# MC33797.net
KiCad netlist of a schematic drawn in Altium Designer
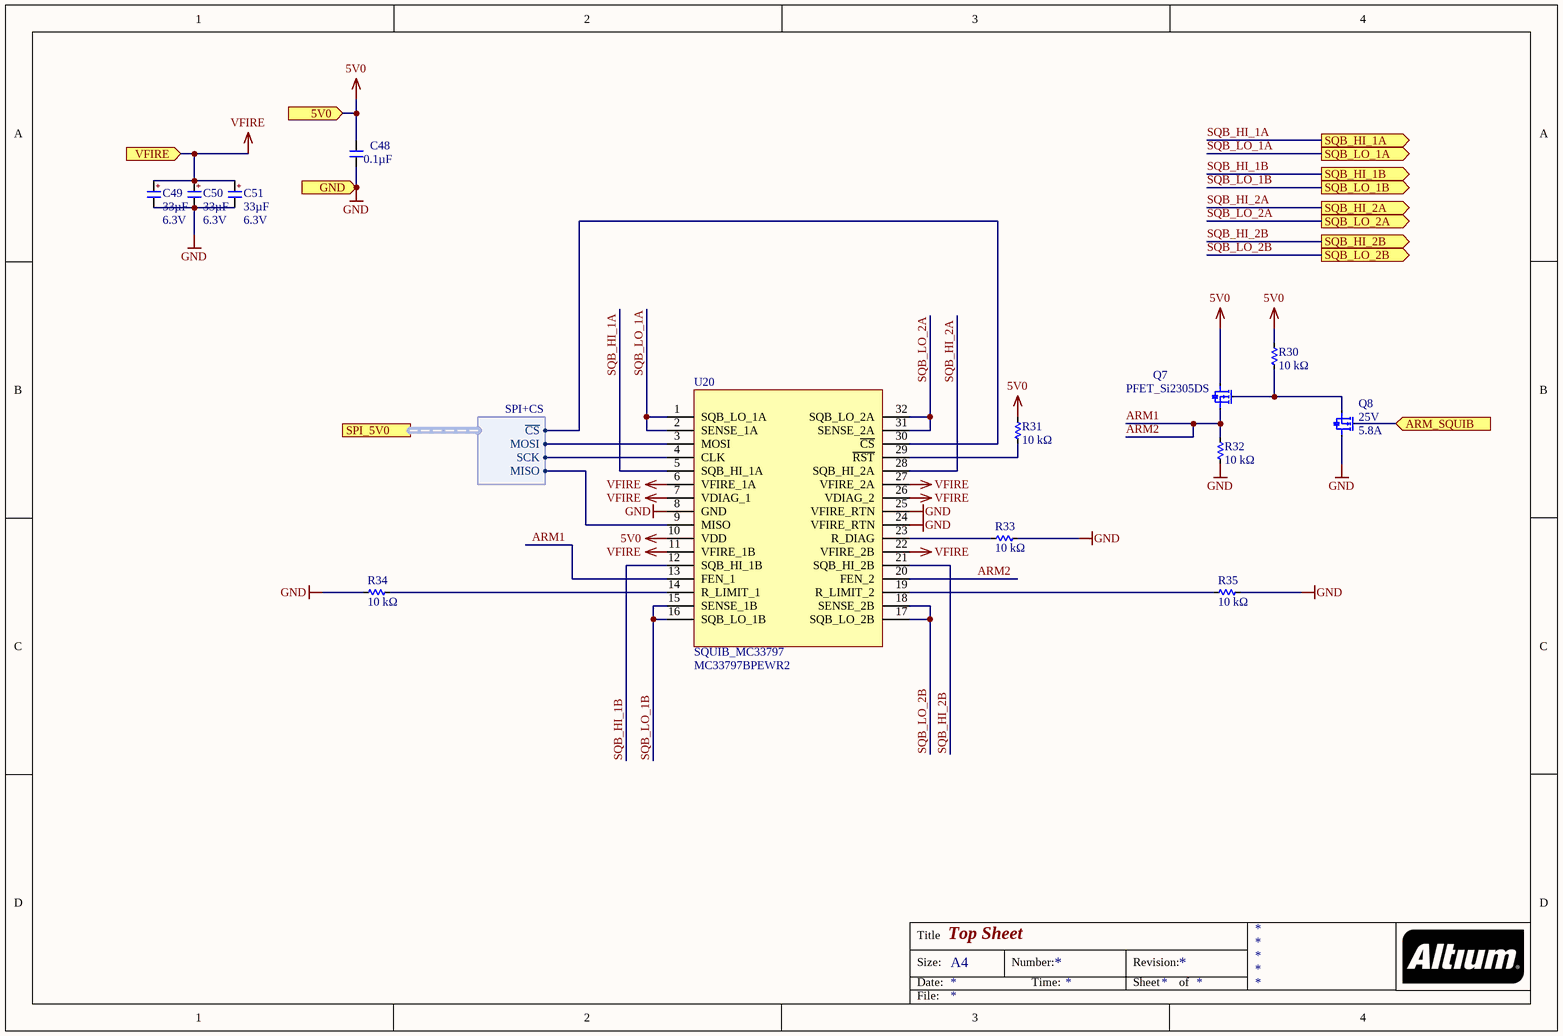
[diagram p0: MC33797.SchDoc]

(export (version "E")
  (design (tool "Eeschema 10.0.6"))
  (components
    (comp (ref "C48")
      (value "CAP_CER_100NF_100V")
      (footprint "C0603")
      (description "CAP CER 0.1UF 100V X7S 0603")
      (fields
        (field (name "MANUFACTURER") "TDK Corporation")
        (field (name "TOLERANCE") "±10%")
        (field (name "CAPACITANCE") "0.1µF")
      )
      (libsource (lib "") (part "Symbol_1"))
    )
    (comp (ref "C49")
      (value "CAP_TANT_33UF")
      (footprint "C1206P")
      (fields
        (field (name "MANUFACTURER") "AVX Corporation")
        (field (name "MANUFACTURER PART NUMBER") "TPSA336K006R0600")
        (field (name "TOLERANCE") "±10%")
        (field (name "CAPACITANCE") "33µF")
        (field (name "VOLTAGE - RATED") "6.3V")
      )
      (libsource (lib "Stanford Student Space Initiative") (part "CAP_TANT_33UF"))
    )
    (comp (ref "C50")
      (value "CAP_TANT_33UF")
      (footprint "C1206P")
      (fields
        (field (name "MANUFACTURER") "AVX Corporation")
        (field (name "MANUFACTURER PART NUMBER") "TPSA336K006R0600")
        (field (name "TOLERANCE") "±10%")
        (field (name "CAPACITANCE") "33µF")
        (field (name "VOLTAGE - RATED") "6.3V")
      )
      (libsource (lib "Stanford Student Space Initiative") (part "CAP_TANT_33UF"))
    )
    (comp (ref "C51")
      (value "CAP_TANT_33UF")
      (footprint "C1206P")
      (fields
        (field (name "MANUFACTURER") "AVX Corporation")
        (field (name "MANUFACTURER PART NUMBER") "TPSA336K006R0600")
        (field (name "TOLERANCE") "±10%")
        (field (name "CAPACITANCE") "33µF")
        (field (name "VOLTAGE - RATED") "6.3V")
      )
      (libsource (lib "Stanford Student Space Initiative") (part "CAP_TANT_33UF"))
    )
    (comp (ref "Q7")
      (value "PFET_Si2305DS")
      (footprint "3SOT23")
      (description "MOSFET P-CH")
      (libsource (lib "Stanford Student Space Initiative") (part "PFET_Si2305DS"))
    )
    (comp (ref "Q8")
      (value "NFET_IRFML8244TRPBF")
      (footprint "3SOT23")
      (description "MOSFET N-CH 25V 5.8A SOT23")
      (fields
        (field (name "MANUFACTURER") "International Rectifier")
        (field (name "MANUFACTURER PART NUMBER") "IRFML8244TRPBF")
        (field (name "DRAIN TO SOURCE VOLTAGE (VDSS)") "25V")
        (field (name "CURRENT - CONTINUOUS DRAIN (ID) @ 25° C") "5.8A")
      )
      (libsource (lib "Stanford Student Space Initiative") (part "Symbol"))
    )
    (comp (ref "R30")
      (value "311-10.0KHRCT-ND")
      (footprint "R0603")
      (description "RES SMD 10K OHM 1% 1/10W 0603")
      (fields
        (field (name "RESISTANCE") "10 kΩ")
        (field (name "MANUFACTURER PART NUMBER") "RC0603FR-0710KL")
        (field (name "MANUFACTURER") "Yageo")
      )
      (libsource (lib "Stanford Student Space Initiative") (part "__template_resistor"))
    )
    (comp (ref "R31")
      (value "311-10.0KHRCT-ND")
      (footprint "R0603")
      (description "RES SMD 10K OHM 1% 1/10W 0603")
      (fields
        (field (name "RESISTANCE") "10 kΩ")
        (field (name "MANUFACTURER PART NUMBER") "RC0603FR-0710KL")
        (field (name "MANUFACTURER") "Yageo")
      )
      (libsource (lib "Stanford Student Space Initiative") (part "__template_resistor"))
    )
    (comp (ref "R32")
      (value "311-10.0KHRCT-ND")
      (footprint "R0603")
      (description "RES SMD 10K OHM 1% 1/10W 0603")
      (fields
        (field (name "RESISTANCE") "10 kΩ")
        (field (name "MANUFACTURER PART NUMBER") "RC0603FR-0710KL")
        (field (name "MANUFACTURER") "Yageo")
      )
      (libsource (lib "Stanford Student Space Initiative") (part "__template_resistor"))
    )
    (comp (ref "R33")
      (value "311-10.0KHRCT-ND")
      (footprint "R0603")
      (description "RES SMD 10K OHM 1% 1/10W 0603")
      (fields
        (field (name "RESISTANCE") "10 kΩ")
        (field (name "MANUFACTURER PART NUMBER") "RC0603FR-0710KL")
        (field (name "MANUFACTURER") "Yageo")
      )
      (libsource (lib "Stanford Student Space Initiative") (part "__template_resistor"))
    )
    (comp (ref "R34")
      (value "311-10.0KHRCT-ND")
      (footprint "R0603")
      (description "RES SMD 10K OHM 1% 1/10W 0603")
      (fields
        (field (name "RESISTANCE") "10 kΩ")
        (field (name "MANUFACTURER PART NUMBER") "RC0603FR-0710KL")
        (field (name "MANUFACTURER") "Yageo")
      )
      (libsource (lib "Stanford Student Space Initiative") (part "__template_resistor"))
    )
    (comp (ref "R35")
      (value "311-10.0KHRCT-ND")
      (footprint "R0603")
      (description "RES SMD 10K OHM 1% 1/10W 0603")
      (fields
        (field (name "RESISTANCE") "10 kΩ")
        (field (name "MANUFACTURER PART NUMBER") "RC0603FR-0710KL")
        (field (name "MANUFACTURER") "Yageo")
      )
      (libsource (lib "Stanford Student Space Initiative") (part "__template_resistor"))
    )
    (comp (ref "U20")
      (value "SQUIB_MC33797")
      (footprint "SOT1762-1")
      (fields
        (field (name "MANUFACTURER") "NXP USA Inc.")
        (field (name "MANUFACTURER PART NUMBER") "MC33797BPEWR2")
      )
      (libsource (lib "Stanford Student Space Initiative") (part "SQUIB_MC33797"))
    )
  )
  (nets
    (net (code "2") (name "/ARM1") (class "Default")
      (node (ref "Q7") (pin "2") (pintype "passive"))
      (node (ref "R32") (pin "2") (pinfunction "2_2") (pintype "passive"))
      (node (ref "U20") (pin "13") (pinfunction "FEN_1_13") (pintype "passive"))
      (node (ref "U20") (pin "20") (pinfunction "FEN_2_20") (pintype "passive"))
    )
    (net (code "3") (name "/ARM_SQUIB") (class "Default") (node (ref "Q8") (pin "1") (pintype "passive")))
    (net (code "4") (name "/MISO") (class "Default")
      (node (ref "U20") (pin "9") (pinfunction "MISO_9") (pintype "passive"))
    )
    (net (code "5") (name "/MOSI") (class "Default")
      (node (ref "U20") (pin "3") (pinfunction "MOSI_3") (pintype "passive"))
    )
    (net (code "6") (name "/SCK") (class "Default")
      (node (ref "U20") (pin "4") (pinfunction "CLK_4") (pintype "passive"))
    )
    (net (code "7") (name "/SQB_HI_1A") (class "Default")
      (node (ref "U20") (pin "5") (pinfunction "SQB_HI_1A_5") (pintype "passive"))
    )
    (net (code "8") (name "/SQB_HI_1B") (class "Default")
      (node (ref "U20") (pin "12") (pinfunction "SQB_HI_1B_12") (pintype "passive"))
    )
    (net (code "9") (name "/SQB_HI_2A") (class "Default")
      (node (ref "U20") (pin "28") (pinfunction "SQB_HI_2A_28") (pintype "passive"))
    )
    (net (code "10") (name "/SQB_HI_2B") (class "Default")
      (node (ref "U20") (pin "21") (pinfunction "SQB_HI_2B_21") (pintype "passive"))
    )
    (net (code "11") (name "/SQB_LO_1A") (class "Default")
      (node (ref "U20") (pin "1") (pinfunction "SQB_LO_1A_1") (pintype "passive"))
      (node (ref "U20") (pin "2") (pinfunction "SENSE_1A_2") (pintype "passive"))
    )
    (net (code "12") (name "/SQB_LO_1B") (class "Default")
      (node (ref "U20") (pin "15") (pinfunction "SENSE_1B_15") (pintype "passive"))
      (node (ref "U20") (pin "16") (pinfunction "SQB_LO_1B_16") (pintype "passive"))
    )
    (net (code "13") (name "/SQB_LO_2A") (class "Default")
      (node (ref "U20") (pin "31") (pinfunction "SENSE_2A_31") (pintype "passive"))
      (node (ref "U20") (pin "32") (pinfunction "SQB_LO_2A_32") (pintype "passive"))
    )
    (net (code "14") (name "/SQB_LO_2B") (class "Default")
      (node (ref "U20") (pin "17") (pinfunction "SQB_LO_2B_17") (pintype "passive"))
      (node (ref "U20") (pin "18") (pinfunction "SENSE_2B_18") (pintype "passive"))
    )
    (net (code "16") (name "/~{CS}") (class "Default")
      (node (ref "U20") (pin "30") (pinfunction "~{CS}_30") (pintype "passive"))
    )
    (net (code "17") (name "5V0") (class "Default")
      (node (ref "C48") (pin "1") (pintype "passive"))
      (node (ref "Q7") (pin "3") (pintype "passive"))
      (node (ref "R30") (pin "2") (pinfunction "2_2") (pintype "passive"))
      (node (ref "R31") (pin "2") (pinfunction "2_2") (pintype "passive"))
      (node (ref "U20") (pin "10") (pinfunction "VDD_10") (pintype "passive"))
    )
    (net (code "18") (name "GND") (class "Default")
      (node (ref "C48") (pin "2") (pintype "passive"))
      (node (ref "C49") (pin "2") (pintype "passive"))
      (node (ref "C50") (pin "2") (pintype "passive"))
      (node (ref "C51") (pin "2") (pintype "passive"))
      (node (ref "Q8") (pin "3") (pintype "passive"))
      (node (ref "R32") (pin "1") (pinfunction "1_1") (pintype "passive"))
      (node (ref "R33") (pin "2") (pinfunction "2_2") (pintype "passive"))
      (node (ref "R34") (pin "1") (pinfunction "1_1") (pintype "passive"))
      (node (ref "R35") (pin "2") (pinfunction "2_2") (pintype "passive"))
      (node (ref "U20") (pin "24") (pinfunction "VFIRE_RTN_24") (pintype "passive"))
      (node (ref "U20") (pin "25") (pinfunction "VFIRE_RTN_25") (pintype "passive"))
      (node (ref "U20") (pin "8") (pinfunction "GND_8") (pintype "passive"))
    )
    (net (code "19") (name "Net-(Q7-Pad1)") (class "Default")
      (node (ref "Q7") (pin "1") (pintype "passive"))
      (node (ref "Q8") (pin "2") (pintype "passive"))
      (node (ref "R30") (pin "1") (pinfunction "1_1") (pintype "passive"))
    )
    (net (code "20") (name "Net-(U20-R_DIAG)") (class "Default")
      (node (ref "R33") (pin "1") (pinfunction "1_1") (pintype "passive"))
      (node (ref "U20") (pin "23") (pinfunction "R_DIAG_23") (pintype "passive"))
    )
    (net (code "21") (name "Net-(U20-R_LIMIT_1)") (class "Default")
      (node (ref "R34") (pin "2") (pinfunction "2_2") (pintype "passive"))
      (node (ref "U20") (pin "14") (pinfunction "R_LIMIT_1_14") (pintype "passive"))
    )
    (net (code "22") (name "Net-(U20-R_LIMIT_2)") (class "Default")
      (node (ref "R35") (pin "1") (pinfunction "1_1") (pintype "passive"))
      (node (ref "U20") (pin "19") (pinfunction "R_LIMIT_2_19") (pintype "passive"))
    )
    (net (code "23") (name "Net-(U20-~{RST})") (class "Default")
      (node (ref "R31") (pin "1") (pinfunction "1_1") (pintype "passive"))
      (node (ref "U20") (pin "29") (pinfunction "~{RST}_29") (pintype "passive"))
    )
    (net (code "24") (name "VFIRE") (class "Default")
      (node (ref "C49") (pin "1") (pintype "passive"))
      (node (ref "C50") (pin "1") (pintype "passive"))
      (node (ref "C51") (pin "1") (pintype "passive"))
      (node (ref "U20") (pin "11") (pinfunction "VFIRE_1B_11") (pintype "passive"))
      (node (ref "U20") (pin "22") (pinfunction "VFIRE_2B_22") (pintype "passive"))
      (node (ref "U20") (pin "26") (pinfunction "VDIAG_2_26") (pintype "passive"))
      (node (ref "U20") (pin "27") (pinfunction "VFIRE_2A_27") (pintype "passive"))
      (node (ref "U20") (pin "6") (pinfunction "VFIRE_1A_6") (pintype "passive"))
      (node (ref "U20") (pin "7") (pinfunction "VDIAG_1_7") (pintype "passive"))
    )
  )
)
